# AVR.net
KiCad netlist of a schematic drawn in Altium Designer
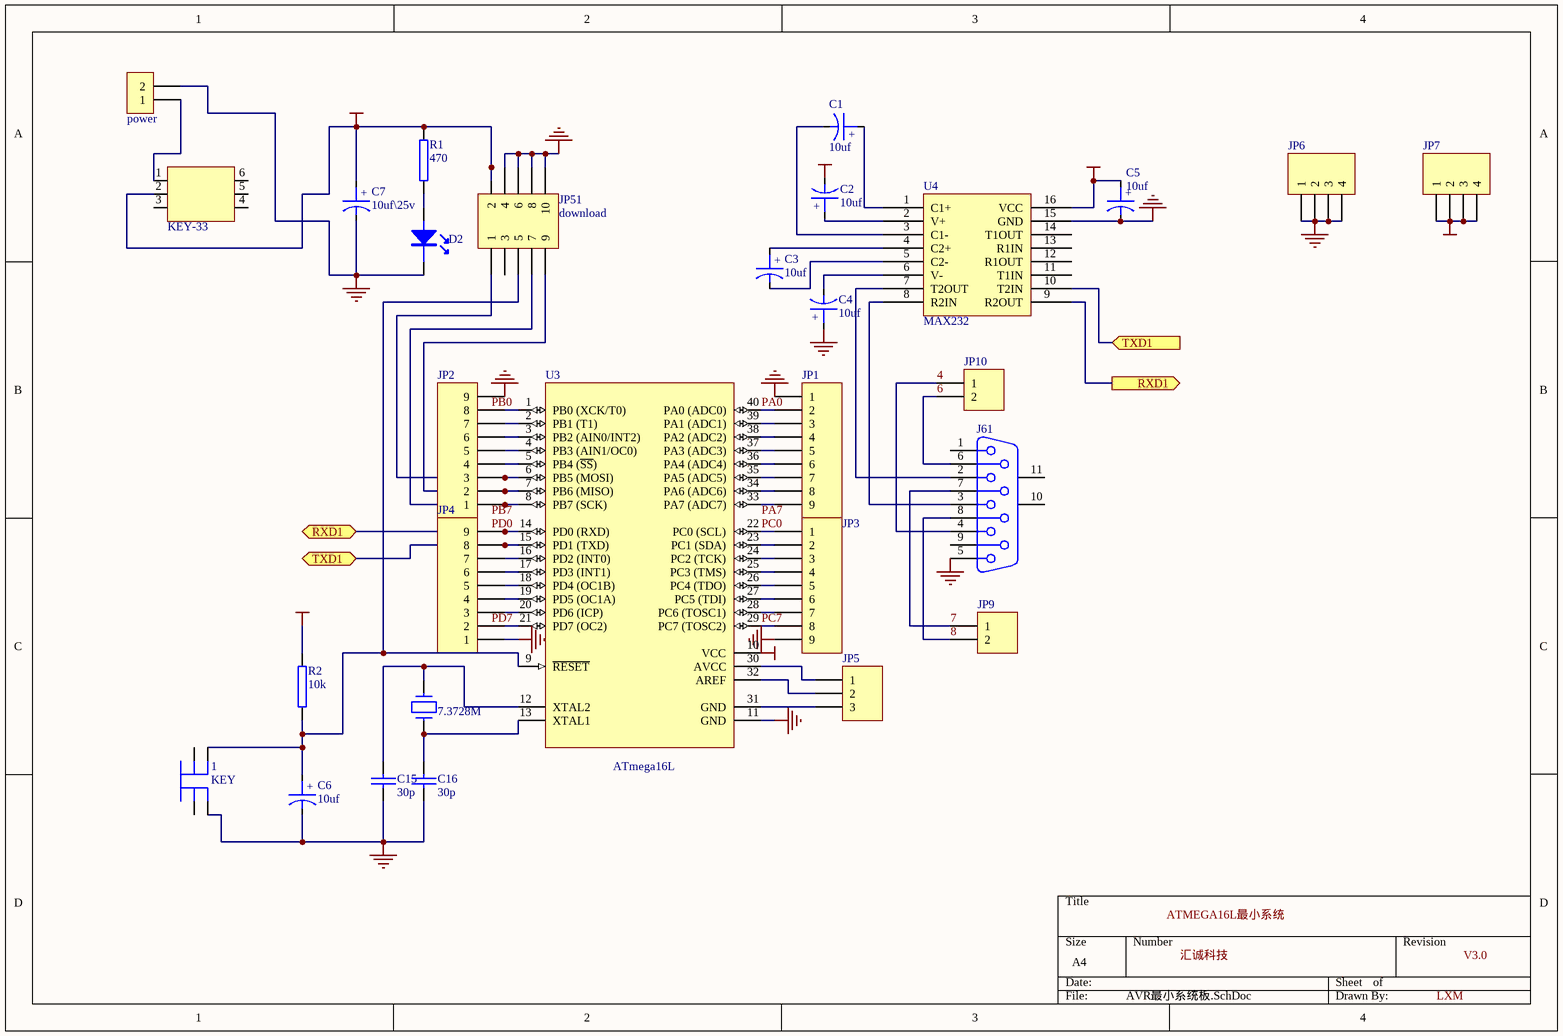
[diagram p0: AVR最小系统板.SchDoc]

(export (version "E")
  (design (tool "Eeschema 10.0.6"))
  (components
    (comp (ref "1") (value "KEY") (footprint "KEY-1") (libsource (lib "OldCow1 (1)") (part "KEY")))
    (comp (ref "11") (value "power") (footprint "power1") (libsource (lib "OldCow1 (1)") (part "power")))
    (comp (ref "C1")
      (value "10uf")
      (footprint "cap2")
      (description "Capacitor")
      (libsource (lib "*") (part "CAPACITOR POL"))
    )
    (comp (ref "C2")
      (value "10uf")
      (footprint "cap2")
      (description "Capacitor")
      (libsource (lib "*") (part "CAPACITOR POL"))
    )
    (comp (ref "C3")
      (value "10uf")
      (footprint "cap2")
      (description "Capacitor")
      (libsource (lib "*") (part "CAPACITOR POL"))
    )
    (comp (ref "C4")
      (value "10uf")
      (footprint "cap2")
      (description "Capacitor")
      (libsource (lib "*") (part "CAPACITOR POL"))
    )
    (comp (ref "C5")
      (value "10uf")
      (footprint "cap2")
      (description "Capacitor")
      (libsource (lib "*") (part "CAPACITOR POL"))
    )
    (comp (ref "C6")
      (value "10uf")
      (footprint "cap2")
      (description "Capacitor")
      (libsource (lib "*") (part "CAPACITOR POL"))
    )
    (comp (ref "C7")
      (value "10u~{f}25v")
      (footprint "cap2")
      (description "Capacitor")
      (libsource (lib "OldCow1 (1)") (part "CAPACITOR POL"))
    )
    (comp (ref "C15")
      (value "30p")
      (footprint "RAD0.3")
      (description "Capacitor")
      (libsource (lib "*") (part "CAP"))
    )
    (comp (ref "C16")
      (value "30p")
      (footprint "RAD0.3")
      (description "Capacitor")
      (libsource (lib "*") (part "CAP"))
    )
    (comp (ref "D2") (value "LED") (footprint "LED") (libsource (lib "OldCow1 (1)") (part "LED")))
    (comp (ref "J61")
      (value "D Connector 9")
      (footprint "DSUB1.385-2H9")
      (description "Receptacle Assembly, 9 Position, Right Angle")
      (fields (field (name "PUBLISHER") "Altium Limited"))
      (libsource (lib "Miscellaneous Connectors") (part "D Connector 9"))
    )
    (comp (ref "JP1")
      (value "~")
      (footprint "HDR1X9")
      (description "Header, 9-Pin")
      (fields (field (name "PUBLISHER") "Altium Limited"))
      (libsource (lib "Miscellaneous Connectors") (part "Header 9"))
    )
    (comp (ref "JP2")
      (value "~")
      (footprint "HDR1X9")
      (description "Header, 9-Pin")
      (fields (field (name "PUBLISHER") "Altium Limited"))
      (libsource (lib "") (part "Header 9_1"))
    )
    (comp (ref "JP3")
      (value "~")
      (footprint "HDR1X9")
      (description "Header, 9-Pin")
      (fields (field (name "PUBLISHER") "Altium Limited"))
      (libsource (lib "Miscellaneous Connectors") (part "Header 9"))
    )
    (comp (ref "JP4")
      (value "~")
      (footprint "HDR1X9")
      (description "Header, 9-Pin")
      (fields (field (name "PUBLISHER") "Altium Limited"))
      (libsource (lib "") (part "Header 9_1"))
    )
    (comp (ref "JP5")
      (value "~")
      (footprint "HDR1X3")
      (description "Header, 3-Pin")
      (fields (field (name "PUBLISHER") "Altium Limited"))
      (libsource (lib "Miscellaneous Connectors") (part "Header 3"))
    )
    (comp (ref "JP6")
      (value "~")
      (footprint "HDR1X4")
      (description "Header, 4-Pin")
      (fields (field (name "PUBLISHER") "Altium Limited"))
      (libsource (lib "Miscellaneous Connectors") (part "Header 4"))
    )
    (comp (ref "JP7")
      (value "~")
      (footprint "HDR1X4")
      (description "Header, 4-Pin")
      (fields (field (name "PUBLISHER") "Altium Limited"))
      (libsource (lib "Miscellaneous Connectors") (part "Header 4"))
    )
    (comp (ref "JP9")
      (value "~")
      (footprint "HDR1X2")
      (description "Header, 2-Pin")
      (fields (field (name "PUBLISHER") "Altium Limited"))
      (libsource (lib "Miscellaneous Connectors") (part "Header 2"))
    )
    (comp (ref "JP10")
      (value "Header 3")
      (footprint "HDR1X2")
      (description "Header, 2-Pin")
      (fields (field (name "PUBLISHER") "Altium Limited"))
      (libsource (lib "Miscellaneous Connectors") (part "Header 2"))
    )
    (comp (ref "JP51")
      (value "download")
      (footprint "HDR2X5")
      (description "Header, 5-Pin, Dual row")
      (fields (field (name "PUBLISHER") "Altium Limited"))
      (libsource (lib "Miscellaneous Connectors") (part "Header 5X2"))
    )
    (comp (ref "R1") (value "470") (footprint "AXIAL0.4") (libsource (lib "*") (part "RES2")))
    (comp (ref "R2") (value "10k") (footprint "AXIAL0.4") (libsource (lib "*") (part "RES2")))
    (comp (ref "RT") (value "KEY-33") (footprint "KEY-2") (libsource (lib "OldCow1 (1)") (part "KEY-33")))
    (comp (ref "U3")
      (value "ATmega16L")
      (footprint "40P6")
      (description "8-Bit AVR Microcontroller with 16K Bytes of In-System Programmable Flash Memory")
      (fields (field (name "PUBLISHER") "Altium Limited"))
      (libsource (lib "Atmel Microcontroller 8-Bit AVR") (part "ATmega16L-8PI"))
    )
    (comp (ref "U4") (value "MAX232") (footprint "DIP16") (libsource (lib "*") (part "MAX232")))
    (comp (ref "Y1")
      (value "7.3728M")
      (footprint "CRYSTAL")
      (description "Crystal")
      (libsource (lib "*") (part "CRYSTAL"))
    )
  )
  (nets
    (net (code "1") (name "/4") (class "Default")
      (node (ref "J61") (pin "4") (pinfunction "4_4") (pintype "passive"))
      (node (ref "JP10") (pin "1") (pinfunction "1_1") (pintype "passive"))
    )
    (net (code "2") (name "/6") (class "Default")
      (node (ref "J61") (pin "6") (pinfunction "6_6") (pintype "passive"))
      (node (ref "JP10") (pin "2") (pinfunction "2_2") (pintype "passive"))
    )
    (net (code "3") (name "/7") (class "Default")
      (node (ref "J61") (pin "7") (pinfunction "7_7") (pintype "passive"))
      (node (ref "JP9") (pin "1") (pinfunction "1_1") (pintype "passive"))
    )
    (net (code "4") (name "/8") (class "Default")
      (node (ref "J61") (pin "8") (pinfunction "8_8") (pintype "passive"))
      (node (ref "JP9") (pin "2") (pinfunction "2_2") (pintype "passive"))
    )
    (net (code "8") (name "/PA0") (class "Default")
      (node (ref "JP1") (pin "2") (pinfunction "2_2") (pintype "passive"))
      (node (ref "U3") (pin "40") (pinfunction "PA0_(ADC0)_40") (pintype "bidirectional"))
    )
    (net (code "12") (name "/PC0") (class "Default")
      (node (ref "JP3") (pin "1") (pinfunction "1_1") (pintype "passive"))
      (node (ref "U3") (pin "22") (pinfunction "PC0_(SCL)_22") (pintype "bidirectional"))
    )
    (net (code "13") (name "/PC7") (class "Default")
      (node (ref "JP3") (pin "8") (pinfunction "8_8") (pintype "passive"))
      (node (ref "U3") (pin "29") (pinfunction "PC7_(TOSC2)_29") (pintype "bidirectional"))
    )
    (net (code "14") (name "/PD0") (class "Default")
      (node (ref "JP4") (pin "9") (pinfunction "9_9") (pintype "passive"))
      (node (ref "U3") (pin "14") (pinfunction "PD0_(RXD)_14") (pintype "bidirectional"))
      (node (ref "U4") (pin "9") (pinfunction "R2OUT_9") (pintype "passive"))
    )
    (net (code "16") (name "/TXD1") (class "Default")
      (node (ref "JP4") (pin "8") (pinfunction "8_8") (pintype "passive"))
      (node (ref "U3") (pin "15") (pinfunction "PD1_(TXD)_15") (pintype "bidirectional"))
      (node (ref "U4") (pin "10") (pinfunction "T2IN_10") (pintype "passive"))
    )
    (net (code "19") (name "GND") (class "Default")
      (node (ref "1") (pin "1") (pinfunction "1_1") (pintype "passive"))
      (node (ref "11") (pin "2") (pinfunction "2_2") (pintype "passive"))
      (node (ref "C15") (pin "2") (pinfunction "2_2") (pintype "passive"))
      (node (ref "C16") (pin "2") (pinfunction "2_2") (pintype "passive"))
      (node (ref "C4") (pin "1") (pinfunction "1_1") (pintype "passive"))
      (node (ref "C5") (pin "2") (pinfunction "2_2") (pintype "passive"))
      (node (ref "C6") (pin "2") (pinfunction "2_2") (pintype "passive"))
      (node (ref "C7") (pin "2") (pinfunction "2_2") (pintype "passive"))
      (node (ref "D2") (pin "2") (pinfunction "K_2") (pintype "passive"))
      (node (ref "J61") (pin "5") (pinfunction "5_5") (pintype "passive"))
      (node (ref "JP1") (pin "1") (pinfunction "1_1") (pintype "passive"))
      (node (ref "JP2") (pin "9") (pinfunction "9_9") (pintype "passive"))
      (node (ref "JP3") (pin "9") (pinfunction "9_9") (pintype "passive"))
      (node (ref "JP4") (pin "1") (pinfunction "1_1") (pintype "passive"))
      (node (ref "JP51") (pin "10") (pinfunction "10_10") (pintype "passive"))
      (node (ref "JP51") (pin "4") (pinfunction "4_4") (pintype "passive"))
      (node (ref "JP51") (pin "6") (pinfunction "6_6") (pintype "passive"))
      (node (ref "JP51") (pin "8") (pinfunction "8_8") (pintype "passive"))
      (node (ref "JP6") (pin "1") (pinfunction "1_1") (pintype "passive"))
      (node (ref "JP6") (pin "2") (pinfunction "2_2") (pintype "passive"))
      (node (ref "JP6") (pin "3") (pinfunction "3_3") (pintype "passive"))
      (node (ref "JP6") (pin "4") (pinfunction "4_4") (pintype "passive"))
      (node (ref "U3") (pin "11") (pinfunction "GND_11") (pintype "power_in"))
      (node (ref "U4") (pin "15") (pinfunction "GND_15") (pintype "passive"))
    )
    (net (code "20") (name "Net-(11-Pad1)") (class "Default")
      (node (ref "11") (pin "1") (pinfunction "1_1") (pintype "passive"))
      (node (ref "RT") (pin "1") (pintype "passive"))
    )
    (net (code "21") (name "Net-(D2-A)") (class "Default")
      (node (ref "D2") (pin "1") (pinfunction "A_1") (pintype "passive"))
      (node (ref "R1") (pin "2") (pinfunction "2_2") (pintype "passive"))
    )
    (net (code "22") (name "Net-(JP5-Pad3)") (class "Default")
      (node (ref "JP5") (pin "3") (pinfunction "3_3") (pintype "passive"))
      (node (ref "U3") (pin "31") (pinfunction "GND_31") (pintype "power_in"))
    )
    (net (code "23") (name "Net-(U3-AREF)") (class "Default")
      (node (ref "JP5") (pin "2") (pinfunction "2_2") (pintype "passive"))
      (node (ref "U3") (pin "32") (pinfunction "AREF_32") (pintype "passive"))
    )
    (net (code "24") (name "Net-(U3-AVCC)") (class "Default")
      (node (ref "JP5") (pin "1") (pinfunction "1_1") (pintype "passive"))
      (node (ref "U3") (pin "30") (pinfunction "AVCC_30") (pintype "power_in"))
    )
    (net (code "25") (name "Net-(U3-PA1_(ADC1))") (class "Default")
      (node (ref "JP1") (pin "3") (pinfunction "3_3") (pintype "passive"))
      (node (ref "U3") (pin "39") (pinfunction "PA1_(ADC1)_39") (pintype "bidirectional"))
    )
    (net (code "26") (name "Net-(U3-PA2_(ADC2))") (class "Default")
      (node (ref "JP1") (pin "4") (pinfunction "4_4") (pintype "passive"))
      (node (ref "U3") (pin "38") (pinfunction "PA2_(ADC2)_38") (pintype "bidirectional"))
    )
    (net (code "27") (name "Net-(U3-PA3_(ADC3))") (class "Default")
      (node (ref "JP1") (pin "5") (pinfunction "5_5") (pintype "passive"))
      (node (ref "U3") (pin "37") (pinfunction "PA3_(ADC3)_37") (pintype "bidirectional"))
    )
    (net (code "28") (name "Net-(U3-PA4_(ADC4))") (class "Default")
      (node (ref "JP1") (pin "6") (pinfunction "6_6") (pintype "passive"))
      (node (ref "U3") (pin "36") (pinfunction "PA4_(ADC4)_36") (pintype "bidirectional"))
    )
    (net (code "29") (name "Net-(U3-PA5_(ADC5))") (class "Default")
      (node (ref "JP1") (pin "7") (pinfunction "7_7") (pintype "passive"))
      (node (ref "U3") (pin "35") (pinfunction "PA5_(ADC5)_35") (pintype "bidirectional"))
    )
    (net (code "30") (name "Net-(U3-PA6_(ADC6))") (class "Default")
      (node (ref "JP1") (pin "8") (pinfunction "8_8") (pintype "passive"))
      (node (ref "U3") (pin "34") (pinfunction "PA6_(ADC6)_34") (pintype "bidirectional"))
    )
    (net (code "31") (name "Net-(U3-PA7_(ADC7))") (class "Default")
      (node (ref "JP1") (pin "9") (pinfunction "9_9") (pintype "passive"))
      (node (ref "U3") (pin "33") (pinfunction "PA7_(ADC7)_33") (pintype "bidirectional"))
    )
    (net (code "32") (name "Net-(U3-PB0_(XCK{slash}T0))") (class "Default")
      (node (ref "JP2") (pin "8") (pinfunction "8_8") (pintype "passive"))
      (node (ref "U3") (pin "1") (pinfunction "PB0_(XCK/T0)_1") (pintype "bidirectional"))
    )
    (net (code "33") (name "Net-(U3-PB1_(T1))") (class "Default")
      (node (ref "JP2") (pin "7") (pinfunction "7_7") (pintype "passive"))
      (node (ref "U3") (pin "2") (pinfunction "PB1_(T1)_2") (pintype "bidirectional"))
    )
    (net (code "34") (name "Net-(U3-PB2_(AIN0{slash}INT2))") (class "Default")
      (node (ref "JP2") (pin "6") (pinfunction "6_6") (pintype "passive"))
      (node (ref "U3") (pin "3") (pinfunction "PB2_(AIN0/INT2)_3") (pintype "bidirectional"))
    )
    (net (code "35") (name "Net-(U3-PB3_(AIN1{slash}OC0))") (class "Default")
      (node (ref "JP2") (pin "5") (pinfunction "5_5") (pintype "passive"))
      (node (ref "U3") (pin "4") (pinfunction "PB3_(AIN1/OC0)_4") (pintype "bidirectional"))
    )
    (net (code "36") (name "Net-(U3-PB4_(~{SS}))") (class "Default")
      (node (ref "JP2") (pin "4") (pinfunction "4_4") (pintype "passive"))
      (node (ref "U3") (pin "5") (pinfunction "PB4_(~{SS})_5") (pintype "bidirectional"))
    )
    (net (code "37") (name "Net-(U3-PB5_(MOSI))") (class "Default")
      (node (ref "JP2") (pin "3") (pinfunction "3_3") (pintype "passive"))
      (node (ref "JP51") (pin "1") (pinfunction "1_1") (pintype "passive"))
      (node (ref "U3") (pin "6") (pinfunction "PB5_(MOSI)_6") (pintype "bidirectional"))
    )
    (net (code "38") (name "Net-(U3-PB6_(MISO))") (class "Default")
      (node (ref "JP2") (pin "2") (pinfunction "2_2") (pintype "passive"))
      (node (ref "JP51") (pin "9") (pinfunction "9_9") (pintype "passive"))
      (node (ref "U3") (pin "7") (pinfunction "PB6_(MISO)_7") (pintype "bidirectional"))
    )
    (net (code "39") (name "Net-(U3-PB7_(SCK))") (class "Default")
      (node (ref "JP2") (pin "1") (pinfunction "1_1") (pintype "passive"))
      (node (ref "JP51") (pin "7") (pinfunction "7_7") (pintype "passive"))
      (node (ref "U3") (pin "8") (pinfunction "PB7_(SCK)_8") (pintype "bidirectional"))
    )
    (net (code "40") (name "Net-(U3-PC1_(SDA))") (class "Default")
      (node (ref "JP3") (pin "2") (pinfunction "2_2") (pintype "passive"))
      (node (ref "U3") (pin "23") (pinfunction "PC1_(SDA)_23") (pintype "bidirectional"))
    )
    (net (code "41") (name "Net-(U3-PC2_(TCK))") (class "Default")
      (node (ref "JP3") (pin "3") (pinfunction "3_3") (pintype "passive"))
      (node (ref "U3") (pin "24") (pinfunction "PC2_(TCK)_24") (pintype "bidirectional"))
    )
    (net (code "42") (name "Net-(U3-PC3_(TMS))") (class "Default")
      (node (ref "JP3") (pin "4") (pinfunction "4_4") (pintype "passive"))
      (node (ref "U3") (pin "25") (pinfunction "PC3_(TMS)_25") (pintype "bidirectional"))
    )
    (net (code "43") (name "Net-(U3-PC4_(TDO))") (class "Default")
      (node (ref "JP3") (pin "5") (pinfunction "5_5") (pintype "passive"))
      (node (ref "U3") (pin "26") (pinfunction "PC4_(TDO)_26") (pintype "bidirectional"))
    )
    (net (code "44") (name "Net-(U3-PC5_(TDI))") (class "Default")
      (node (ref "JP3") (pin "6") (pinfunction "6_6") (pintype "passive"))
      (node (ref "U3") (pin "27") (pinfunction "PC5_(TDI)_27") (pintype "bidirectional"))
    )
    (net (code "45") (name "Net-(U3-PC6_(TOSC1))") (class "Default")
      (node (ref "JP3") (pin "7") (pinfunction "7_7") (pintype "passive"))
      (node (ref "U3") (pin "28") (pinfunction "PC6_(TOSC1)_28") (pintype "bidirectional"))
    )
    (net (code "46") (name "Net-(U3-PD2_(INT0))") (class "Default")
      (node (ref "JP4") (pin "7") (pinfunction "7_7") (pintype "passive"))
      (node (ref "U3") (pin "16") (pinfunction "PD2_(INT0)_16") (pintype "bidirectional"))
    )
    (net (code "47") (name "Net-(U3-PD3_(INT1))") (class "Default")
      (node (ref "JP4") (pin "6") (pinfunction "6_6") (pintype "passive"))
      (node (ref "U3") (pin "17") (pinfunction "PD3_(INT1)_17") (pintype "bidirectional"))
    )
    (net (code "48") (name "Net-(U3-PD4_(OC1B))") (class "Default")
      (node (ref "JP4") (pin "5") (pinfunction "5_5") (pintype "passive"))
      (node (ref "U3") (pin "18") (pinfunction "PD4_(OC1B)_18") (pintype "bidirectional"))
    )
    (net (code "49") (name "Net-(U3-PD5_(OC1A))") (class "Default")
      (node (ref "JP4") (pin "4") (pinfunction "4_4") (pintype "passive"))
      (node (ref "U3") (pin "19") (pinfunction "PD5_(OC1A)_19") (pintype "bidirectional"))
    )
    (net (code "50") (name "Net-(U3-PD6_(ICP))") (class "Default")
      (node (ref "JP4") (pin "3") (pinfunction "3_3") (pintype "passive"))
      (node (ref "U3") (pin "20") (pinfunction "PD6_(ICP)_20") (pintype "bidirectional"))
    )
    (net (code "51") (name "Net-(U3-PD7_(OC2))") (class "Default")
      (node (ref "JP4") (pin "2") (pinfunction "2_2") (pintype "passive"))
      (node (ref "U3") (pin "21") (pinfunction "PD7_(OC2)_21") (pintype "bidirectional"))
    )
    (net (code "52") (name "Net-(U3-XTAL1)") (class "Default")
      (node (ref "C16") (pin "1") (pinfunction "1_1") (pintype "passive"))
      (node (ref "U3") (pin "13") (pinfunction "XTAL1_13") (pintype "passive"))
      (node (ref "Y1") (pin "2") (pinfunction "2_2") (pintype "passive"))
    )
    (net (code "53") (name "Net-(U3-XTAL2)") (class "Default")
      (node (ref "C15") (pin "1") (pinfunction "1_1") (pintype "passive"))
      (node (ref "U3") (pin "12") (pinfunction "XTAL2_12") (pintype "passive"))
      (node (ref "Y1") (pin "1") (pinfunction "1_1") (pintype "passive"))
    )
    (net (code "54") (name "Net-(U3-~{RESET})") (class "Default")
      (node (ref "1") (pin "3") (pinfunction "3_3") (pintype "passive"))
      (node (ref "C6") (pin "1") (pinfunction "1_1") (pintype "passive"))
      (node (ref "JP51") (pin "5") (pinfunction "5_5") (pintype "passive"))
      (node (ref "R2") (pin "2") (pinfunction "2_2") (pintype "passive"))
      (node (ref "U3") (pin "9") (pinfunction "~{RESET}_9") (pintype "input"))
    )
    (net (code "55") (name "Net-(U4-C1+)") (class "Default")
      (node (ref "C1") (pin "1") (pinfunction "1_1") (pintype "passive"))
      (node (ref "U4") (pin "1") (pinfunction "C1+_1") (pintype "passive"))
    )
    (net (code "56") (name "Net-(U4-C1-)") (class "Default")
      (node (ref "C1") (pin "2") (pinfunction "2_2") (pintype "passive"))
      (node (ref "U4") (pin "3") (pinfunction "C1-_3") (pintype "passive"))
    )
    (net (code "57") (name "Net-(U4-C2+)") (class "Default")
      (node (ref "C3") (pin "1") (pinfunction "1_1") (pintype "passive"))
      (node (ref "U4") (pin "4") (pinfunction "C2+_4") (pintype "passive"))
    )
    (net (code "58") (name "Net-(U4-C2-)") (class "Default")
      (node (ref "C3") (pin "2") (pinfunction "2_2") (pintype "passive"))
      (node (ref "U4") (pin "5") (pinfunction "C2-_5") (pintype "passive"))
    )
    (net (code "59") (name "Net-(U4-R2IN)") (class "Default")
      (node (ref "J61") (pin "3") (pinfunction "3_3") (pintype "passive"))
      (node (ref "U4") (pin "8") (pinfunction "R2IN_8") (pintype "passive"))
    )
    (net (code "60") (name "Net-(U4-T2OUT)") (class "Default")
      (node (ref "J61") (pin "2") (pinfunction "2_2") (pintype "passive"))
      (node (ref "U4") (pin "7") (pinfunction "T2OUT_7") (pintype "passive"))
    )
    (net (code "61") (name "Net-(U4-V+)") (class "Default")
      (node (ref "C2") (pin "1") (pinfunction "1_1") (pintype "passive"))
      (node (ref "U4") (pin "2") (pinfunction "V+_2") (pintype "passive"))
    )
    (net (code "62") (name "Net-(U4-V-)") (class "Default")
      (node (ref "C4") (pin "2") (pinfunction "2_2") (pintype "passive"))
      (node (ref "U4") (pin "6") (pinfunction "V-_6") (pintype "passive"))
    )
    (net (code "63") (name "VCC") (class "Default")
      (node (ref "C2") (pin "2") (pinfunction "2_2") (pintype "passive"))
      (node (ref "C5") (pin "1") (pinfunction "1_1") (pintype "passive"))
      (node (ref "C7") (pin "1") (pinfunction "1_1") (pintype "passive"))
      (node (ref "JP51") (pin "2") (pinfunction "2_2") (pintype "passive"))
      (node (ref "JP7") (pin "1") (pinfunction "1_1") (pintype "passive"))
      (node (ref "JP7") (pin "2") (pinfunction "2_2") (pintype "passive"))
      (node (ref "JP7") (pin "3") (pinfunction "3_3") (pintype "passive"))
      (node (ref "JP7") (pin "4") (pinfunction "4_4") (pintype "passive"))
      (node (ref "R1") (pin "1") (pinfunction "1_1") (pintype "passive"))
      (node (ref "R2") (pin "1") (pinfunction "1_1") (pintype "passive"))
      (node (ref "RT") (pin "2") (pintype "passive"))
      (node (ref "U3") (pin "10") (pinfunction "VCC_10") (pintype "power_in"))
      (node (ref "U4") (pin "16") (pinfunction "VCC_16") (pintype "passive"))
    )
    (net (code "64") (name "unconnected-(1-Pad0)") (class "Default")
      (node (ref "1") (pin "0") (pinfunction "0_0") (pintype "passive"))
    )
    (net (code "65") (name "unconnected-(1-Pad2)") (class "Default")
      (node (ref "1") (pin "2") (pinfunction "2_2") (pintype "passive"))
    )
    (net (code "66") (name "unconnected-(J61-MH1-Pad10)") (class "Default")
      (node (ref "J61") (pin "10") (pinfunction "MH1_10") (pintype "passive"))
    )
    (net (code "67") (name "unconnected-(J61-MH2-Pad11)") (class "Default")
      (node (ref "J61") (pin "11") (pinfunction "MH2_11") (pintype "passive"))
    )
    (net (code "68") (name "unconnected-(J61-Pad1)") (class "Default")
      (node (ref "J61") (pin "1") (pinfunction "1_1") (pintype "passive"))
    )
    (net (code "69") (name "unconnected-(J61-Pad9)") (class "Default")
      (node (ref "J61") (pin "9") (pinfunction "9_9") (pintype "passive"))
    )
    (net (code "70") (name "unconnected-(JP51-Pad3)") (class "Default")
      (node (ref "JP51") (pin "3") (pinfunction "3_3") (pintype "passive"))
    )
    (net (code "71") (name "unconnected-(RT-Pad3)") (class "Default")
      (node (ref "RT") (pin "3") (pintype "passive"))
    )
    (net (code "72") (name "unconnected-(RT-Pad4)") (class "Default")
      (node (ref "RT") (pin "4") (pintype "passive"))
    )
    (net (code "73") (name "unconnected-(RT-Pad5)") (class "Default")
      (node (ref "RT") (pin "5") (pintype "passive"))
    )
    (net (code "74") (name "unconnected-(RT-Pad6)") (class "Default")
      (node (ref "RT") (pin "6") (pintype "passive"))
    )
    (net (code "75") (name "unconnected-(U4-R1IN-Pad13)") (class "Default")
      (node (ref "U4") (pin "13") (pinfunction "R1IN_13") (pintype "passive"))
    )
    (net (code "76") (name "unconnected-(U4-R1OUT-Pad12)") (class "Default")
      (node (ref "U4") (pin "12") (pinfunction "R1OUT_12") (pintype "passive"))
    )
    (net (code "77") (name "unconnected-(U4-T1IN-Pad11)") (class "Default")
      (node (ref "U4") (pin "11") (pinfunction "T1IN_11") (pintype "passive"))
    )
    (net (code "78") (name "unconnected-(U4-T1OUT-Pad14)") (class "Default")
      (node (ref "U4") (pin "14") (pinfunction "T1OUT_14") (pintype "passive"))
    )
  )
)
